# T35_6_DDR3.net
KiCad netlist of a schematic drawn in Altium Designer
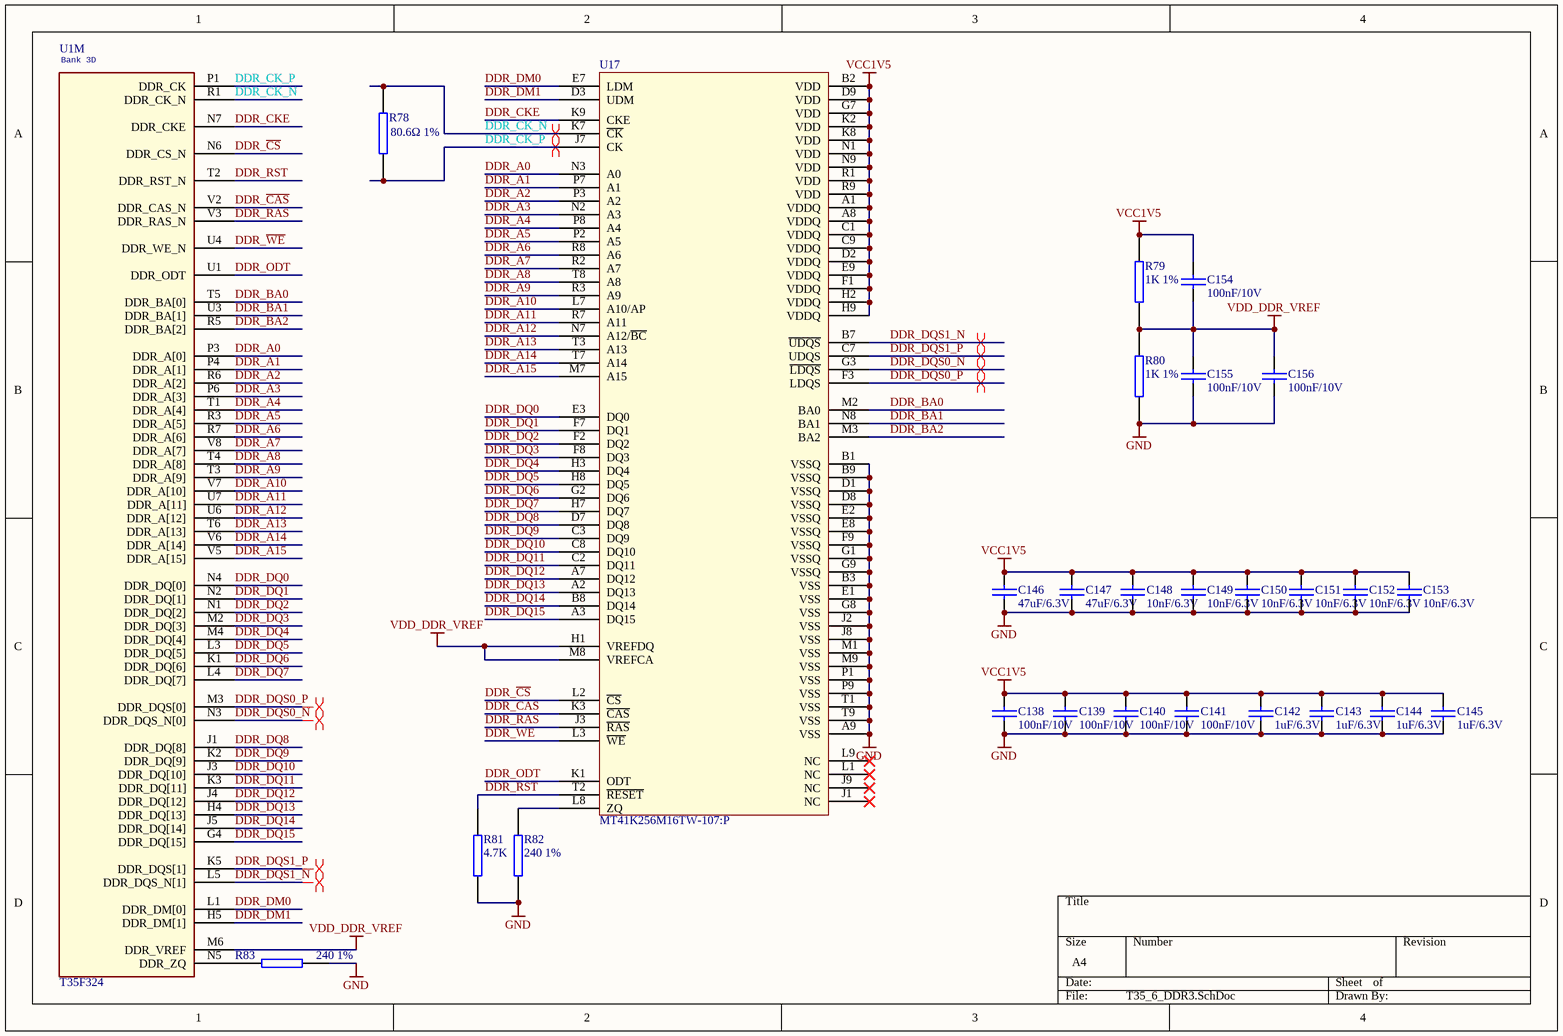
[diagram p0: T35_6_DDR3.SchDoc]

(export (version "E")
  (design (tool "Eeschema 10.0.6"))
  (components
    (comp (ref "C138")
      (value "100nF/10V")
      (footprint "0201CS")
      (description "贴片电容")
      (libsource (lib "*") (part "CAP"))
    )
    (comp (ref "C139")
      (value "100nF/10V")
      (footprint "0201CS")
      (description "贴片电容")
      (libsource (lib "*") (part "CAP"))
    )
    (comp (ref "C140")
      (value "100nF/10V")
      (footprint "0201CS")
      (description "贴片电容")
      (libsource (lib "*") (part "CAP"))
    )
    (comp (ref "C141")
      (value "100nF/10V")
      (footprint "0201CS")
      (description "贴片电容")
      (libsource (lib "*") (part "CAP"))
    )
    (comp (ref "C142")
      (value "1uF/6.3V")
      (footprint "0201CS")
      (description "贴片电容")
      (libsource (lib "*") (part "CAP"))
    )
    (comp (ref "C143")
      (value "1uF/6.3V")
      (footprint "0201CS")
      (description "贴片电容")
      (libsource (lib "*") (part "CAP"))
    )
    (comp (ref "C144")
      (value "1uF/6.3V")
      (footprint "0201CS")
      (description "贴片电容")
      (libsource (lib "*") (part "CAP"))
    )
    (comp (ref "C145")
      (value "1uF/6.3V")
      (footprint "0201CS")
      (description "贴片电容")
      (libsource (lib "*") (part "CAP"))
    )
    (comp (ref "C146")
      (value "47uF/6.3V")
      (footprint "0603CS")
      (description "贴片电容")
      (libsource (lib "*") (part "CAP"))
    )
    (comp (ref "C147")
      (value "47uF/6.3V")
      (footprint "0603CS")
      (description "贴片电容")
      (libsource (lib "*") (part "CAP"))
    )
    (comp (ref "C148")
      (value "10nF/6.3V")
      (footprint "0201CS")
      (description "贴片电容")
      (libsource (lib "*") (part "CAP"))
    )
    (comp (ref "C149")
      (value "10nF/6.3V")
      (footprint "0201CS")
      (description "贴片电容")
      (libsource (lib "*") (part "CAP"))
    )
    (comp (ref "C150")
      (value "10nF/6.3V")
      (footprint "0201CS")
      (description "贴片电容")
      (libsource (lib "*") (part "CAP"))
    )
    (comp (ref "C151")
      (value "10nF/6.3V")
      (footprint "0201CS")
      (description "贴片电容")
      (libsource (lib "*") (part "CAP"))
    )
    (comp (ref "C152")
      (value "10nF/6.3V")
      (footprint "0201CS")
      (description "贴片电容")
      (libsource (lib "*") (part "CAP"))
    )
    (comp (ref "C153")
      (value "10nF/6.3V")
      (footprint "0201CS")
      (description "贴片电容")
      (libsource (lib "*") (part "CAP"))
    )
    (comp (ref "C154")
      (value "100nF/10V")
      (footprint "0201CS")
      (description "贴片电容")
      (libsource (lib "*") (part "CAP"))
    )
    (comp (ref "C155")
      (value "100nF/10V")
      (footprint "0201CS")
      (description "贴片电容")
      (libsource (lib "*") (part "CAP"))
    )
    (comp (ref "C156")
      (value "100nF/10V")
      (footprint "0201CS")
      (description "贴片电容")
      (libsource (lib "*") (part "CAP"))
    )
    (comp (ref "R78")
      (value "80.6Ω 1%")
      (footprint "0402RS")
      (description "贴片电阻")
      (libsource (lib "*") (part "RES2"))
    )
    (comp (ref "R79")
      (value "1K 1%")
      (footprint "0402RS")
      (description "贴片电阻")
      (libsource (lib "*") (part "RES2"))
    )
    (comp (ref "R80")
      (value "1K 1%")
      (footprint "0402RS")
      (description "贴片电阻")
      (libsource (lib "*") (part "RES2"))
    )
    (comp (ref "R81")
      (value "4.7K")
      (footprint "0402RS")
      (description "贴片电阻")
      (libsource (lib "*") (part "RES2"))
    )
    (comp (ref "R82")
      (value "240 1%")
      (footprint "0201RS")
      (description "贴片电阻")
      (libsource (lib "*") (part "RES2"))
    )
    (comp (ref "R83")
      (value "240 1%")
      (footprint "0201RS")
      (description "贴片电阻")
      (libsource (lib "*") (part "RES2"))
    )
    (comp (ref "U1")
      (value "T35F324")
      (footprint "T35-F324-BGA100P9X9-81A")
      (description "FPGA芯片")
      (libsource (lib "orcadt35-v1.0_Library") (part "T35F324"))
    )
    (comp (ref "U17")
      (value "MT41K256M16TW-107:P")
      (footprint "MICT-TNA-96")
      (description "DDR3芯片")
      (libsource (lib "QHY_LIB_SCH_AD10") (part "MT41K512M16HA-125IT"))
    )
  )
  (nets
    (net (code "1") (name "/DDR_A0") (class "Default")
      (node (ref "U1") (pin "P3") (pinfunction "DDR_A[0]_P3") (pintype "passive"))
      (node (ref "U17") (pin "N3") (pinfunction "A0_N3") (pintype "passive"))
    )
    (net (code "2") (name "/DDR_A1") (class "Default")
      (node (ref "U1") (pin "P4") (pinfunction "DDR_A[1]_P4") (pintype "passive"))
      (node (ref "U17") (pin "P7") (pinfunction "A1_P7") (pintype "passive"))
    )
    (net (code "3") (name "/DDR_A2") (class "Default")
      (node (ref "U1") (pin "R6") (pinfunction "DDR_A[2]_R6") (pintype "passive"))
      (node (ref "U17") (pin "P3") (pinfunction "A2_P3") (pintype "passive"))
    )
    (net (code "4") (name "/DDR_A3") (class "Default")
      (node (ref "U1") (pin "P6") (pinfunction "DDR_A[3]_P6") (pintype "passive"))
      (node (ref "U17") (pin "N2") (pinfunction "A3_N2") (pintype "passive"))
    )
    (net (code "5") (name "/DDR_A4") (class "Default")
      (node (ref "U1") (pin "T1") (pinfunction "DDR_A[4]_T1") (pintype "passive"))
      (node (ref "U17") (pin "P8") (pinfunction "A4_P8") (pintype "passive"))
    )
    (net (code "6") (name "/DDR_A5") (class "Default")
      (node (ref "U1") (pin "R3") (pinfunction "DDR_A[5]_R3") (pintype "passive"))
      (node (ref "U17") (pin "P2") (pinfunction "A5_P2") (pintype "passive"))
    )
    (net (code "7") (name "/DDR_A6") (class "Default")
      (node (ref "U1") (pin "R7") (pinfunction "DDR_A[6]_R7") (pintype "passive"))
      (node (ref "U17") (pin "R8") (pinfunction "A6_R8") (pintype "passive"))
    )
    (net (code "8") (name "/DDR_A7") (class "Default")
      (node (ref "U1") (pin "V8") (pinfunction "DDR_A[7]_V8") (pintype "passive"))
      (node (ref "U17") (pin "R2") (pinfunction "A7_R2") (pintype "passive"))
    )
    (net (code "9") (name "/DDR_A8") (class "Default")
      (node (ref "U1") (pin "T4") (pinfunction "DDR_A[8]_T4") (pintype "passive"))
      (node (ref "U17") (pin "T8") (pinfunction "A8_T8") (pintype "passive"))
    )
    (net (code "10") (name "/DDR_A9") (class "Default")
      (node (ref "U1") (pin "T3") (pinfunction "DDR_A[9]_T3") (pintype "passive"))
      (node (ref "U17") (pin "R3") (pinfunction "A9_R3") (pintype "passive"))
    )
    (net (code "11") (name "/DDR_A10") (class "Default")
      (node (ref "U1") (pin "V7") (pinfunction "DDR_A[10]_V7") (pintype "passive"))
      (node (ref "U17") (pin "L7") (pinfunction "A10/AP_L7") (pintype "passive"))
    )
    (net (code "12") (name "/DDR_A11") (class "Default")
      (node (ref "U1") (pin "U7") (pinfunction "DDR_A[11]_U7") (pintype "passive"))
      (node (ref "U17") (pin "R7") (pinfunction "A11_R7") (pintype "passive"))
    )
    (net (code "13") (name "/DDR_A12") (class "Default")
      (node (ref "U1") (pin "U6") (pinfunction "DDR_A[12]_U6") (pintype "passive"))
      (node (ref "U17") (pin "N7") (pinfunction "A12/~{BC}_N7") (pintype "passive"))
    )
    (net (code "14") (name "/DDR_A13") (class "Default")
      (node (ref "U1") (pin "T6") (pinfunction "DDR_A[13]_T6") (pintype "passive"))
      (node (ref "U17") (pin "T3") (pinfunction "A13_T3") (pintype "passive"))
    )
    (net (code "15") (name "/DDR_A14") (class "Default")
      (node (ref "U1") (pin "V6") (pinfunction "DDR_A[14]_V6") (pintype "passive"))
      (node (ref "U17") (pin "T7") (pinfunction "A14_T7") (pintype "passive"))
    )
    (net (code "16") (name "/DDR_A15") (class "Default")
      (node (ref "U1") (pin "V5") (pinfunction "DDR_A[15]_V5") (pintype "passive"))
      (node (ref "U17") (pin "M7") (pinfunction "A15_M7") (pintype "passive"))
    )
    (net (code "17") (name "/DDR_BA0") (class "Default")
      (node (ref "U1") (pin "T5") (pinfunction "DDR_BA[0]_T5") (pintype "passive"))
      (node (ref "U17") (pin "M2") (pinfunction "BA0_M2") (pintype "passive"))
    )
    (net (code "18") (name "/DDR_BA1") (class "Default")
      (node (ref "U1") (pin "U3") (pinfunction "DDR_BA[1]_U3") (pintype "passive"))
      (node (ref "U17") (pin "N8") (pinfunction "BA1_N8") (pintype "passive"))
    )
    (net (code "19") (name "/DDR_BA2") (class "Default")
      (node (ref "U1") (pin "R5") (pinfunction "DDR_BA[2]_R5") (pintype "passive"))
      (node (ref "U17") (pin "M3") (pinfunction "BA2_M3") (pintype "passive"))
    )
    (net (code "20") (name "/DDR_CKE") (class "Default")
      (node (ref "U1") (pin "N7") (pinfunction "DDR_CKE_N7") (pintype "passive"))
      (node (ref "U17") (pin "K9") (pinfunction "CKE_K9") (pintype "passive"))
    )
    (net (code "21") (name "/DDR_CK_N") (class "Default")
      (node (ref "R78") (pin "1") (pinfunction "1_1") (pintype "passive"))
      (node (ref "U1") (pin "R1") (pinfunction "DDR_CK_N_R1") (pintype "passive"))
      (node (ref "U17") (pin "K7") (pinfunction "~{CK}_K7") (pintype "passive"))
    )
    (net (code "22") (name "/DDR_CK_P") (class "Default")
      (node (ref "R78") (pin "2") (pinfunction "2_2") (pintype "passive"))
      (node (ref "U1") (pin "P1") (pinfunction "DDR_CK_P1") (pintype "passive"))
      (node (ref "U17") (pin "J7") (pinfunction "CK_J7") (pintype "passive"))
    )
    (net (code "23") (name "/DDR_DM0") (class "Default")
      (node (ref "U1") (pin "L1") (pinfunction "DDR_DM[0]_L1") (pintype "passive"))
      (node (ref "U17") (pin "E7") (pinfunction "LDM_E7") (pintype "passive"))
    )
    (net (code "24") (name "/DDR_DM1") (class "Default")
      (node (ref "U1") (pin "H5") (pinfunction "DDR_DM[1]_H5") (pintype "passive"))
      (node (ref "U17") (pin "D3") (pinfunction "UDM_D3") (pintype "passive"))
    )
    (net (code "25") (name "/DDR_DQ0") (class "Default")
      (node (ref "U1") (pin "N4") (pinfunction "DDR_DQ[0]_N4") (pintype "passive"))
      (node (ref "U17") (pin "E3") (pinfunction "DQ0_E3") (pintype "passive"))
    )
    (net (code "26") (name "/DDR_DQ1") (class "Default")
      (node (ref "U1") (pin "N2") (pinfunction "DDR_DQ[1]_N2") (pintype "passive"))
      (node (ref "U17") (pin "F7") (pinfunction "DQ1_F7") (pintype "passive"))
    )
    (net (code "27") (name "/DDR_DQ2") (class "Default")
      (node (ref "U1") (pin "N1") (pinfunction "DDR_DQ[2]_N1") (pintype "passive"))
      (node (ref "U17") (pin "F2") (pinfunction "DQ2_F2") (pintype "passive"))
    )
    (net (code "28") (name "/DDR_DQ3") (class "Default")
      (node (ref "U1") (pin "M2") (pinfunction "DDR_DQ[3]_M2") (pintype "passive"))
      (node (ref "U17") (pin "F8") (pinfunction "DQ3_F8") (pintype "passive"))
    )
    (net (code "29") (name "/DDR_DQ4") (class "Default")
      (node (ref "U1") (pin "M4") (pinfunction "DDR_DQ[4]_M4") (pintype "passive"))
      (node (ref "U17") (pin "H3") (pinfunction "DQ4_H3") (pintype "passive"))
    )
    (net (code "30") (name "/DDR_DQ5") (class "Default")
      (node (ref "U1") (pin "L3") (pinfunction "DDR_DQ[5]_L3") (pintype "passive"))
      (node (ref "U17") (pin "H8") (pinfunction "DQ5_H8") (pintype "passive"))
    )
    (net (code "31") (name "/DDR_DQ6") (class "Default")
      (node (ref "U1") (pin "K1") (pinfunction "DDR_DQ[6]_K1") (pintype "passive"))
      (node (ref "U17") (pin "G2") (pinfunction "DQ6_G2") (pintype "passive"))
    )
    (net (code "32") (name "/DDR_DQ7") (class "Default")
      (node (ref "U1") (pin "L4") (pinfunction "DDR_DQ[7]_L4") (pintype "passive"))
      (node (ref "U17") (pin "H7") (pinfunction "DQ7_H7") (pintype "passive"))
    )
    (net (code "33") (name "/DDR_DQ8") (class "Default")
      (node (ref "U1") (pin "J1") (pinfunction "DDR_DQ[8]_J1") (pintype "passive"))
      (node (ref "U17") (pin "D7") (pinfunction "DQ8_D7") (pintype "passive"))
    )
    (net (code "34") (name "/DDR_DQ9") (class "Default")
      (node (ref "U1") (pin "K2") (pinfunction "DDR_DQ[9]_K2") (pintype "passive"))
      (node (ref "U17") (pin "C3") (pinfunction "DQ9_C3") (pintype "passive"))
    )
    (net (code "35") (name "/DDR_DQ10") (class "Default")
      (node (ref "U1") (pin "J3") (pinfunction "DDR_DQ[10]_J3") (pintype "passive"))
      (node (ref "U17") (pin "C8") (pinfunction "DQ10_C8") (pintype "passive"))
    )
    (net (code "36") (name "/DDR_DQ11") (class "Default")
      (node (ref "U1") (pin "K3") (pinfunction "DDR_DQ[11]_K3") (pintype "passive"))
      (node (ref "U17") (pin "C2") (pinfunction "DQ11_C2") (pintype "passive"))
    )
    (net (code "37") (name "/DDR_DQ12") (class "Default")
      (node (ref "U1") (pin "J4") (pinfunction "DDR_DQ[12]_J4") (pintype "passive"))
      (node (ref "U17") (pin "A7") (pinfunction "DQ12_A7") (pintype "passive"))
    )
    (net (code "38") (name "/DDR_DQ13") (class "Default")
      (node (ref "U1") (pin "H4") (pinfunction "DDR_DQ[13]_H4") (pintype "passive"))
      (node (ref "U17") (pin "A2") (pinfunction "DQ13_A2") (pintype "passive"))
    )
    (net (code "39") (name "/DDR_DQ14") (class "Default")
      (node (ref "U1") (pin "J5") (pinfunction "DDR_DQ[14]_J5") (pintype "passive"))
      (node (ref "U17") (pin "B8") (pinfunction "DQ14_B8") (pintype "passive"))
    )
    (net (code "40") (name "/DDR_DQ15") (class "Default")
      (node (ref "U1") (pin "G4") (pinfunction "DDR_DQ[15]_G4") (pintype "passive"))
      (node (ref "U17") (pin "A3") (pinfunction "DQ15_A3") (pintype "passive"))
    )
    (net (code "41") (name "/DDR_DQS0_N") (class "Default")
      (node (ref "U1") (pin "N3") (pinfunction "DDR_DQS_N[0]_N3") (pintype "passive"))
      (node (ref "U17") (pin "G3") (pinfunction "~{LDQS}_G3") (pintype "passive"))
    )
    (net (code "42") (name "/DDR_DQS0_P") (class "Default")
      (node (ref "U1") (pin "M3") (pinfunction "DDR_DQS[0]_M3") (pintype "passive"))
      (node (ref "U17") (pin "F3") (pinfunction "LDQS_F3") (pintype "passive"))
    )
    (net (code "43") (name "/DDR_DQS1_N") (class "Default")
      (node (ref "U1") (pin "L5") (pinfunction "DDR_DQS_N[1]_L5") (pintype "passive"))
      (node (ref "U17") (pin "B7") (pinfunction "~{UDQS}_B7") (pintype "passive"))
    )
    (net (code "44") (name "/DDR_DQS1_P") (class "Default")
      (node (ref "U1") (pin "K5") (pinfunction "DDR_DQS[1]_K5") (pintype "passive"))
      (node (ref "U17") (pin "C7") (pinfunction "UDQS_C7") (pintype "passive"))
    )
    (net (code "45") (name "/DDR_ODT") (class "Default")
      (node (ref "U1") (pin "U1") (pinfunction "DDR_ODT_U1") (pintype "passive"))
      (node (ref "U17") (pin "K1") (pinfunction "ODT_K1") (pintype "passive"))
    )
    (net (code "46") (name "/DDR_RST") (class "Default")
      (node (ref "R81") (pin "1") (pinfunction "1_1") (pintype "passive"))
      (node (ref "U1") (pin "T2") (pinfunction "DDR_RST_N_T2") (pintype "passive"))
      (node (ref "U17") (pin "T2") (pinfunction "~{RESET}_T2") (pintype "passive"))
    )
    (net (code "47") (name "/DDR_~{CAS}") (class "Default")
      (node (ref "U1") (pin "V2") (pinfunction "DDR_CAS_N_V2") (pintype "passive"))
      (node (ref "U17") (pin "K3") (pinfunction "~{CAS}_K3") (pintype "passive"))
    )
    (net (code "48") (name "/DDR_~{CS}") (class "Default")
      (node (ref "U1") (pin "N6") (pinfunction "DDR_CS_N_N6") (pintype "passive"))
      (node (ref "U17") (pin "L2") (pinfunction "~{CS}_L2") (pintype "passive"))
    )
    (net (code "49") (name "/DDR_~{RAS}") (class "Default")
      (node (ref "U1") (pin "V3") (pinfunction "DDR_RAS_N_V3") (pintype "passive"))
      (node (ref "U17") (pin "J3") (pinfunction "~{RAS}_J3") (pintype "passive"))
    )
    (net (code "50") (name "/DDR_~{WE}") (class "Default")
      (node (ref "U1") (pin "U4") (pinfunction "DDR_WE_N_U4") (pintype "passive"))
      (node (ref "U17") (pin "L3") (pinfunction "~{WE}_L3") (pintype "passive"))
    )
    (net (code "51") (name "GND") (class "Default")
      (node (ref "C138") (pin "2") (pinfunction "2_2") (pintype "passive"))
      (node (ref "C139") (pin "2") (pinfunction "2_2") (pintype "passive"))
      (node (ref "C140") (pin "2") (pinfunction "2_2") (pintype "passive"))
      (node (ref "C141") (pin "2") (pinfunction "2_2") (pintype "passive"))
      (node (ref "C142") (pin "2") (pinfunction "2_2") (pintype "passive"))
      (node (ref "C143") (pin "2") (pinfunction "2_2") (pintype "passive"))
      (node (ref "C144") (pin "2") (pinfunction "2_2") (pintype "passive"))
      (node (ref "C145") (pin "2") (pinfunction "2_2") (pintype "passive"))
      (node (ref "C146") (pin "2") (pinfunction "2_2") (pintype "passive"))
      (node (ref "C147") (pin "2") (pinfunction "2_2") (pintype "passive"))
      (node (ref "C148") (pin "2") (pinfunction "2_2") (pintype "passive"))
      (node (ref "C149") (pin "2") (pinfunction "2_2") (pintype "passive"))
      (node (ref "C150") (pin "2") (pinfunction "2_2") (pintype "passive"))
      (node (ref "C151") (pin "2") (pinfunction "2_2") (pintype "passive"))
      (node (ref "C152") (pin "2") (pinfunction "2_2") (pintype "passive"))
      (node (ref "C153") (pin "2") (pinfunction "2_2") (pintype "passive"))
      (node (ref "C155") (pin "2") (pinfunction "2_2") (pintype "passive"))
      (node (ref "C156") (pin "2") (pinfunction "2_2") (pintype "passive"))
      (node (ref "R80") (pin "1") (pinfunction "1_1") (pintype "passive"))
      (node (ref "R81") (pin "2") (pinfunction "2_2") (pintype "passive"))
      (node (ref "R82") (pin "2") (pinfunction "2_2") (pintype "passive"))
      (node (ref "R83") (pin "2") (pinfunction "2_2") (pintype "passive"))
      (node (ref "U17") (pin "A9") (pinfunction "VSS_A9") (pintype "passive"))
      (node (ref "U17") (pin "B1") (pinfunction "VSSQ_B1") (pintype "passive"))
      (node (ref "U17") (pin "B3") (pinfunction "VSS_B3") (pintype "passive"))
      (node (ref "U17") (pin "B9") (pinfunction "VSSQ_B9") (pintype "passive"))
      (node (ref "U17") (pin "D1") (pinfunction "VSSQ_D1") (pintype "passive"))
      (node (ref "U17") (pin "D8") (pinfunction "VSSQ_D8") (pintype "passive"))
      (node (ref "U17") (pin "E1") (pinfunction "VSS_E1") (pintype "passive"))
      (node (ref "U17") (pin "E2") (pinfunction "VSSQ_E2") (pintype "passive"))
      (node (ref "U17") (pin "E8") (pinfunction "VSSQ_E8") (pintype "passive"))
      (node (ref "U17") (pin "F9") (pinfunction "VSSQ_F9") (pintype "passive"))
      (node (ref "U17") (pin "G1") (pinfunction "VSSQ_G1") (pintype "passive"))
      (node (ref "U17") (pin "G8") (pinfunction "VSS_G8") (pintype "passive"))
      (node (ref "U17") (pin "G9") (pinfunction "VSSQ_G9") (pintype "passive"))
      (node (ref "U17") (pin "J2") (pinfunction "VSS_J2") (pintype "passive"))
      (node (ref "U17") (pin "J8") (pinfunction "VSS_J8") (pintype "passive"))
      (node (ref "U17") (pin "M1") (pinfunction "VSS_M1") (pintype "passive"))
      (node (ref "U17") (pin "M9") (pinfunction "VSS_M9") (pintype "passive"))
      (node (ref "U17") (pin "P1") (pinfunction "VSS_P1") (pintype "passive"))
      (node (ref "U17") (pin "P9") (pinfunction "VSS_P9") (pintype "passive"))
      (node (ref "U17") (pin "T1") (pinfunction "VSS_T1") (pintype "passive"))
      (node (ref "U17") (pin "T9") (pinfunction "VSS_T9") (pintype "passive"))
    )
    (net (code "52") (name "Net-(U1M-DDR_ZQ)") (class "Default")
      (node (ref "R83") (pin "1") (pinfunction "1_1") (pintype "passive"))
      (node (ref "U1") (pin "N5") (pinfunction "DDR_ZQ_N5") (pintype "passive"))
    )
    (net (code "53") (name "Net-(U17-ZQ)") (class "Default")
      (node (ref "R82") (pin "1") (pinfunction "1_1") (pintype "passive"))
      (node (ref "U17") (pin "L8") (pinfunction "ZQ_L8") (pintype "passive"))
    )
    (net (code "54") (name "VCC1V5") (class "Default")
      (node (ref "C138") (pin "1") (pinfunction "1_1") (pintype "passive"))
      (node (ref "C139") (pin "1") (pinfunction "1_1") (pintype "passive"))
      (node (ref "C140") (pin "1") (pinfunction "1_1") (pintype "passive"))
      (node (ref "C141") (pin "1") (pinfunction "1_1") (pintype "passive"))
      (node (ref "C142") (pin "1") (pinfunction "1_1") (pintype "passive"))
      (node (ref "C143") (pin "1") (pinfunction "1_1") (pintype "passive"))
      (node (ref "C144") (pin "1") (pinfunction "1_1") (pintype "passive"))
      (node (ref "C145") (pin "1") (pinfunction "1_1") (pintype "passive"))
      (node (ref "C146") (pin "1") (pinfunction "1_1") (pintype "passive"))
      (node (ref "C147") (pin "1") (pinfunction "1_1") (pintype "passive"))
      (node (ref "C148") (pin "1") (pinfunction "1_1") (pintype "passive"))
      (node (ref "C149") (pin "1") (pinfunction "1_1") (pintype "passive"))
      (node (ref "C150") (pin "1") (pinfunction "1_1") (pintype "passive"))
      (node (ref "C151") (pin "1") (pinfunction "1_1") (pintype "passive"))
      (node (ref "C152") (pin "1") (pinfunction "1_1") (pintype "passive"))
      (node (ref "C153") (pin "1") (pinfunction "1_1") (pintype "passive"))
      (node (ref "C154") (pin "1") (pinfunction "1_1") (pintype "passive"))
      (node (ref "R79") (pin "2") (pinfunction "2_2") (pintype "passive"))
      (node (ref "U17") (pin "A1") (pinfunction "VDDQ_A1") (pintype "passive"))
      (node (ref "U17") (pin "A8") (pinfunction "VDDQ_A8") (pintype "passive"))
      (node (ref "U17") (pin "B2") (pinfunction "VDD_B2") (pintype "passive"))
      (node (ref "U17") (pin "C1") (pinfunction "VDDQ_C1") (pintype "passive"))
      (node (ref "U17") (pin "C9") (pinfunction "VDDQ_C9") (pintype "passive"))
      (node (ref "U17") (pin "D2") (pinfunction "VDDQ_D2") (pintype "passive"))
      (node (ref "U17") (pin "D9") (pinfunction "VDD_D9") (pintype "passive"))
      (node (ref "U17") (pin "E9") (pinfunction "VDDQ_E9") (pintype "passive"))
      (node (ref "U17") (pin "F1") (pinfunction "VDDQ_F1") (pintype "passive"))
      (node (ref "U17") (pin "G7") (pinfunction "VDD_G7") (pintype "passive"))
      (node (ref "U17") (pin "H2") (pinfunction "VDDQ_H2") (pintype "passive"))
      (node (ref "U17") (pin "H9") (pinfunction "VDDQ_H9") (pintype "passive"))
      (node (ref "U17") (pin "K2") (pinfunction "VDD_K2") (pintype "passive"))
      (node (ref "U17") (pin "K8") (pinfunction "VDD_K8") (pintype "passive"))
      (node (ref "U17") (pin "N1") (pinfunction "VDD_N1") (pintype "passive"))
      (node (ref "U17") (pin "N9") (pinfunction "VDD_N9") (pintype "passive"))
      (node (ref "U17") (pin "R1") (pinfunction "VDD_R1") (pintype "passive"))
      (node (ref "U17") (pin "R9") (pinfunction "VDD_R9") (pintype "passive"))
    )
    (net (code "55") (name "VDD_DDR_VREF") (class "Default")
      (node (ref "C154") (pin "2") (pinfunction "2_2") (pintype "passive"))
      (node (ref "C155") (pin "1") (pinfunction "1_1") (pintype "passive"))
      (node (ref "C156") (pin "1") (pinfunction "1_1") (pintype "passive"))
      (node (ref "R79") (pin "1") (pinfunction "1_1") (pintype "passive"))
      (node (ref "R80") (pin "2") (pinfunction "2_2") (pintype "passive"))
      (node (ref "U1") (pin "M6") (pinfunction "DDR_VREF_M6") (pintype "passive"))
      (node (ref "U17") (pin "H1") (pinfunction "VREFDQ_H1") (pintype "passive"))
      (node (ref "U17") (pin "M8") (pinfunction "VREFCA_M8") (pintype "passive"))
    )
    (net (code "56") (name "unconnected-(U17-NC-PadJ1)") (class "Default")
      (node (ref "U17") (pin "J1") (pinfunction "NC_J1") (pintype "passive+no_connect"))
    )
    (net (code "57") (name "unconnected-(U17-NC-PadJ9)") (class "Default")
      (node (ref "U17") (pin "J9") (pinfunction "NC_J9") (pintype "passive+no_connect"))
    )
    (net (code "58") (name "unconnected-(U17-NC-PadL1)") (class "Default")
      (node (ref "U17") (pin "L1") (pinfunction "NC_L1") (pintype "passive+no_connect"))
    )
    (net (code "59") (name "unconnected-(U17-NC-PadL9)") (class "Default")
      (node (ref "U17") (pin "L9") (pinfunction "NC_L9") (pintype "passive+no_connect"))
    )
  )
)
